# 8Bit-audio-7524-axelb-v2.net
KiCad netlist of a schematic drawn in EAGLE
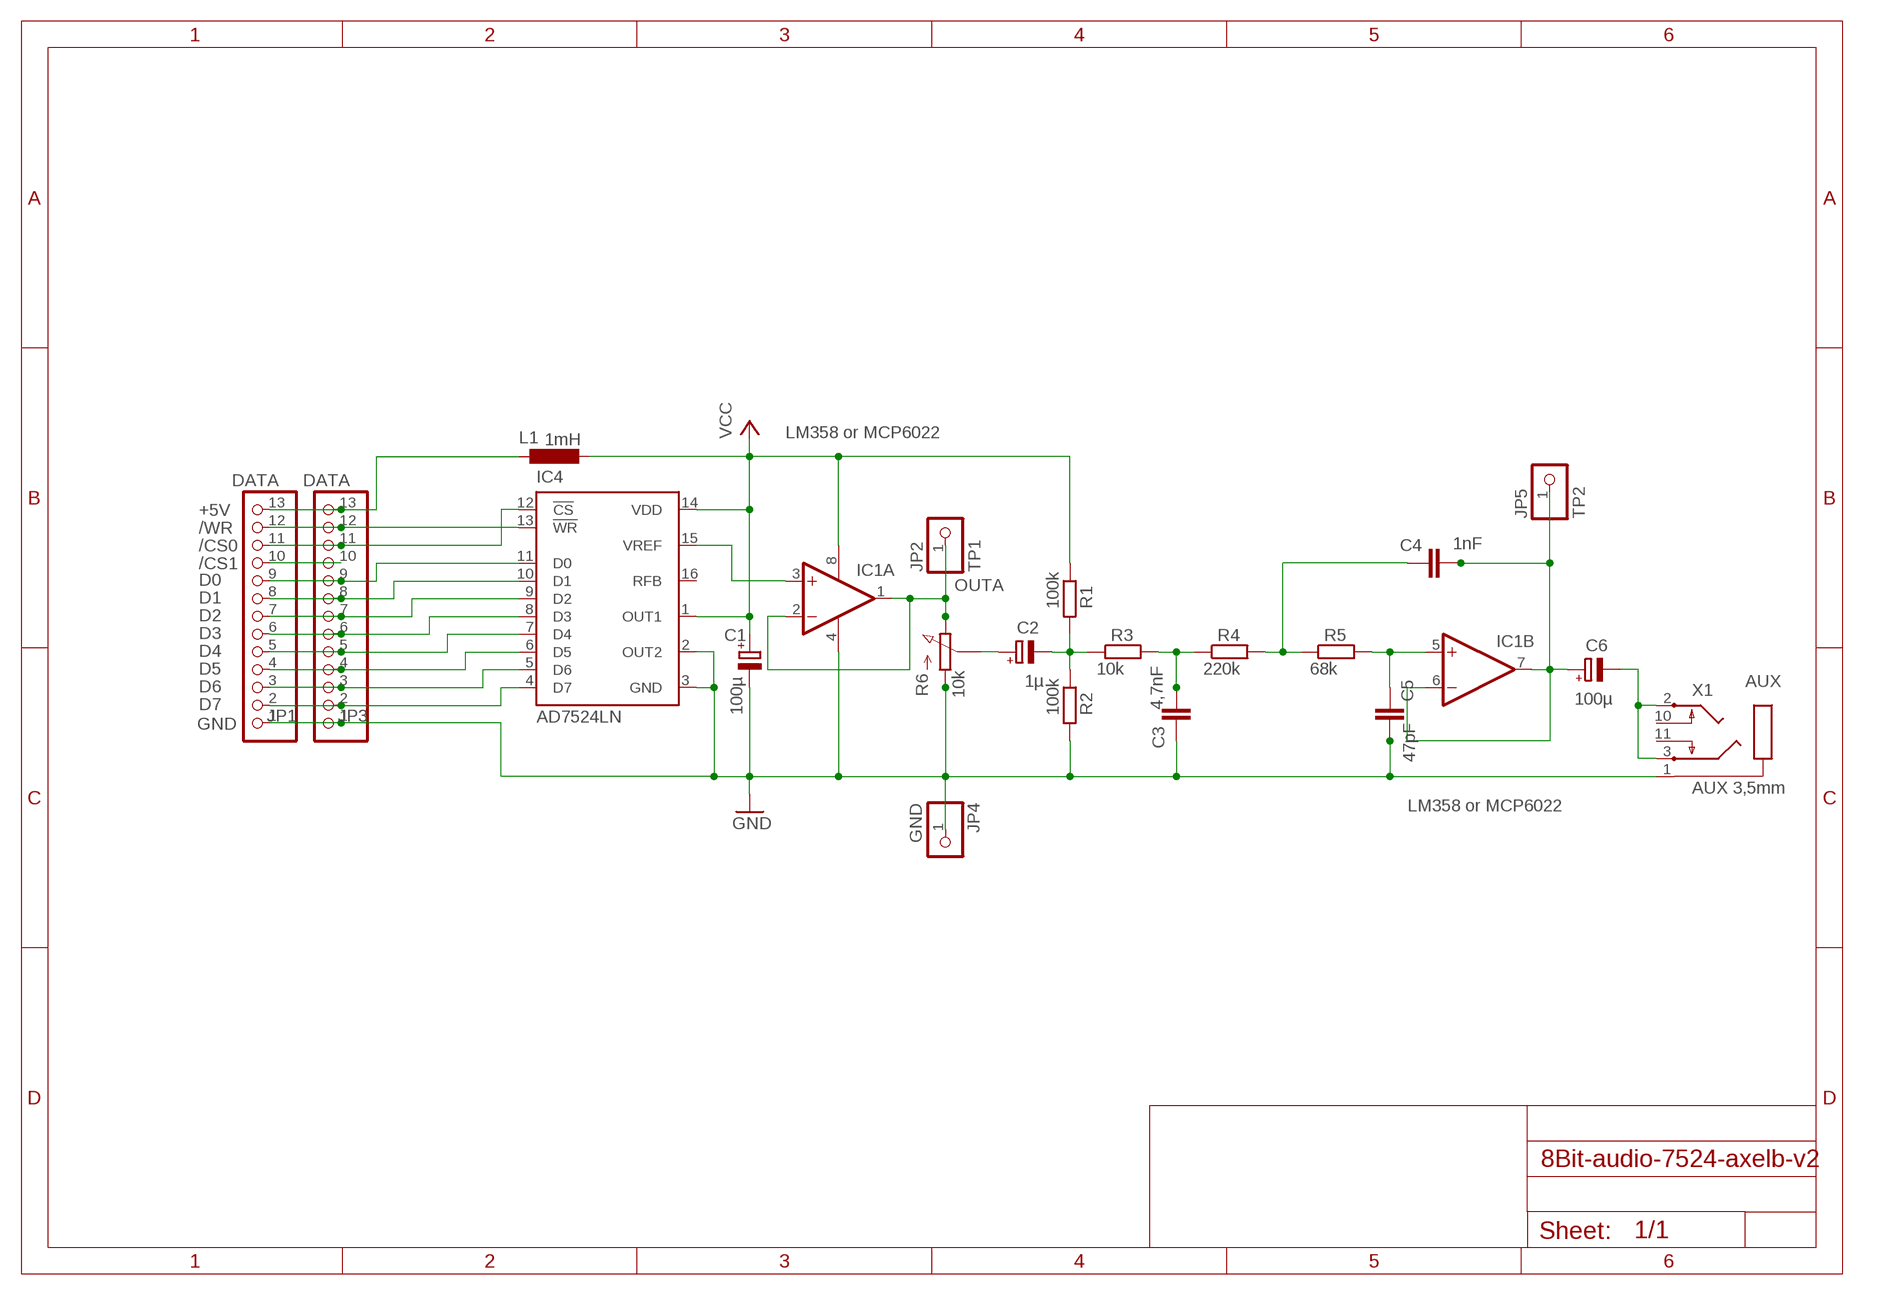
[diagram p0: schematic, sheet 1]

(export (version "E")
  (design (tool "Eeschema 10.0.6"))
  (components
    (comp (ref "C1")
      (value "100µ")
      (footprint "eagle-import:E5-5")
      (libsource (lib "eagle-import") (part "CPOL-EUE5-5"))
    )
    (comp (ref "C2")
      (value "1µ")
      (footprint "eagle-import:E5-5")
      (libsource (lib "eagle-import") (part "CPOL-EUE5-5"))
    )
    (comp (ref "C3")
      (value "4,7nF")
      (footprint "eagle-import:RCL_C025_050-055X075")
      (libsource (lib "eagle-import") (part "RCL_C-EU025_050-055X075"))
    )
    (comp (ref "C4")
      (value "1nF")
      (footprint "eagle-import:RCL_C025_050-055X075")
      (libsource (lib "eagle-import") (part "RCL_C-EU025_050-055X075"))
    )
    (comp (ref "C5")
      (value "47pF")
      (footprint "eagle-import:RCL_C025_050-055X075")
      (libsource (lib "eagle-import") (part "RCL_C-EU025_050-055X075"))
    )
    (comp (ref "C6")
      (value "100µ")
      (footprint "eagle-import:E5-5")
      (libsource (lib "eagle-import") (part "CPOL-EUE5-5"))
    )
    (comp (ref "IC1")
      (value "LM358 or MCP6022")
      (footprint "eagle-import:DIL08")
      (libsource (lib "eagle-import") (part "LM358N"))
    )
    (comp (ref "IC4")
      (value "AD7524LN")
      (footprint "eagle-import:DIL16")
      (fields (field (name "MF") "ALTERA CORPORATION") (field (name "MPN") "AD7524LNZ"))
      (libsource (lib "eagle-import") (part "AD7524NL"))
    )
    (comp (ref "JP1")
      (value "DATA")
      (footprint "eagle-import:1X13")
      (libsource (lib "eagle-import") (part "PINHD-1X13"))
    )
    (comp (ref "JP2")
      (value "TP1")
      (footprint "eagle-import:1X01")
      (libsource (lib "eagle-import") (part "PINHD-1X1"))
    )
    (comp (ref "JP3")
      (value "DATA")
      (footprint "eagle-import:1X13")
      (libsource (lib "eagle-import") (part "PINHD-1X13"))
    )
    (comp (ref "JP4")
      (value "GND")
      (footprint "eagle-import:1X01")
      (libsource (lib "eagle-import") (part "PINHD-1X1"))
    )
    (comp (ref "JP5")
      (value "TP2")
      (footprint "eagle-import:1X01")
      (libsource (lib "eagle-import") (part "PINHD-1X1"))
    )
    (comp (ref "L1")
      (value "1mH")
      (footprint "eagle-import:0207_10")
      (libsource (lib "eagle-import") (part "L-EU0207/10"))
    )
    (comp (ref "R1")
      (value "100k")
      (footprint "eagle-import:0207_10")
      (libsource (lib "eagle-import") (part "R-EU_0207/10"))
    )
    (comp (ref "R2")
      (value "100k")
      (footprint "eagle-import:0207_10")
      (libsource (lib "eagle-import") (part "R-EU_0207/10"))
    )
    (comp (ref "R3")
      (value "10k")
      (footprint "eagle-import:0207_10")
      (libsource (lib "eagle-import") (part "R-EU_0207/10"))
    )
    (comp (ref "R4")
      (value "220k")
      (footprint "eagle-import:0207_10")
      (libsource (lib "eagle-import") (part "R-EU_0207/10"))
    )
    (comp (ref "R5")
      (value "68k")
      (footprint "eagle-import:0207_10")
      (libsource (lib "eagle-import") (part "R-EU_0207/10"))
    )
    (comp (ref "R6")
      (value "10k")
      (footprint "eagle-import:POT_3RP_1610N")
      (libsource (lib "eagle-import") (part "POT_3RP/1610N"))
    )
    (comp (ref "X1")
      (value "AUX 3,5mm")
      (footprint "eagle-import:SJ1-352XN")
      (libsource (lib "eagle-import") (part "CON-SJ1-352XNSJ1-352XN"))
    )
  )
  (nets
    (net (code "1") (name "/+5V") (class "Default")
      (node (ref "JP1") (pin "13") (pinfunction "13_13") (pintype "passive"))
      (node (ref "JP3") (pin "13") (pinfunction "13_13") (pintype "passive"))
      (node (ref "L1") (pin "1") (pinfunction "1_1") (pintype "passive"))
    )
    (net (code "2") (name "/AUX") (class "Default")
      (node (ref "C6") (pin "-") (pinfunction "-_-") (pintype "passive"))
      (node (ref "X1") (pin "2") (pinfunction "2_2") (pintype "passive"))
      (node (ref "X1") (pin "3") (pinfunction "3_3") (pintype "passive"))
    )
    (net (code "3") (name "/D0") (class "Default")
      (node (ref "IC4") (pin "11") (pinfunction "D0_11") (pintype "input"))
      (node (ref "JP1") (pin "9") (pinfunction "9_9") (pintype "passive"))
      (node (ref "JP3") (pin "9") (pinfunction "9_9") (pintype "passive"))
    )
    (net (code "4") (name "/D1") (class "Default")
      (node (ref "IC4") (pin "10") (pinfunction "D1_10") (pintype "input"))
      (node (ref "JP1") (pin "8") (pinfunction "8_8") (pintype "passive"))
      (node (ref "JP3") (pin "8") (pinfunction "8_8") (pintype "passive"))
    )
    (net (code "5") (name "/D2") (class "Default")
      (node (ref "IC4") (pin "9") (pinfunction "D2_9") (pintype "input"))
      (node (ref "JP1") (pin "7") (pinfunction "7_7") (pintype "passive"))
      (node (ref "JP3") (pin "7") (pinfunction "7_7") (pintype "passive"))
    )
    (net (code "6") (name "/D3") (class "Default")
      (node (ref "IC4") (pin "8") (pinfunction "D3_8") (pintype "input"))
      (node (ref "JP1") (pin "6") (pinfunction "6_6") (pintype "passive"))
      (node (ref "JP3") (pin "6") (pinfunction "6_6") (pintype "passive"))
    )
    (net (code "7") (name "/D4") (class "Default")
      (node (ref "IC4") (pin "7") (pinfunction "D4_7") (pintype "input"))
      (node (ref "JP1") (pin "5") (pinfunction "5_5") (pintype "passive"))
      (node (ref "JP3") (pin "5") (pinfunction "5_5") (pintype "passive"))
    )
    (net (code "8") (name "/D5") (class "Default")
      (node (ref "IC4") (pin "6") (pinfunction "D5_6") (pintype "input"))
      (node (ref "JP1") (pin "4") (pinfunction "4_4") (pintype "passive"))
      (node (ref "JP3") (pin "4") (pinfunction "4_4") (pintype "passive"))
    )
    (net (code "9") (name "/D6") (class "Default")
      (node (ref "IC4") (pin "5") (pinfunction "D6_5") (pintype "input"))
      (node (ref "JP1") (pin "3") (pinfunction "3_3") (pintype "passive"))
      (node (ref "JP3") (pin "3") (pinfunction "3_3") (pintype "passive"))
    )
    (net (code "10") (name "/D7") (class "Default")
      (node (ref "IC4") (pin "4") (pinfunction "D7_4") (pintype "input"))
      (node (ref "JP1") (pin "2") (pinfunction "2_2") (pintype "passive"))
      (node (ref "JP3") (pin "2") (pinfunction "2_2") (pintype "passive"))
    )
    (net (code "11") (name "/OUTA") (class "Default")
      (node (ref "IC1") (pin "1") (pinfunction "OUT_1") (pintype "output"))
      (node (ref "IC1") (pin "2") (pinfunction "-IN_2") (pintype "input"))
      (node (ref "JP2") (pin "1") (pinfunction "1_1") (pintype "passive"))
      (node (ref "R6") (pin "E1") (pinfunction "E1_E1") (pintype "passive"))
      (node (ref "R6") (pin "E2") (pinfunction "E2_E2") (pintype "passive"))
    )
    (net (code "12") (name "/{slash}CS0") (class "Default")
      (node (ref "IC4") (pin "12") (pinfunction "~{CS}_12") (pintype "input"))
      (node (ref "JP1") (pin "11") (pinfunction "11_11") (pintype "passive"))
      (node (ref "JP3") (pin "11") (pinfunction "11_11") (pintype "passive"))
    )
    (net (code "13") (name "/{slash}CS1") (class "Default")
      (node (ref "JP1") (pin "10") (pinfunction "10_10") (pintype "passive"))
      (node (ref "JP3") (pin "10") (pinfunction "10_10") (pintype "passive"))
    )
    (net (code "14") (name "/{slash}WR") (class "Default")
      (node (ref "IC4") (pin "13") (pinfunction "~{WR}_13") (pintype "input"))
      (node (ref "JP1") (pin "12") (pinfunction "12_12") (pintype "passive"))
      (node (ref "JP3") (pin "12") (pinfunction "12_12") (pintype "passive"))
    )
    (net (code "15") (name "GND") (class "Default")
      (node (ref "C1") (pin "-") (pinfunction "-_-") (pintype "passive"))
      (node (ref "C3") (pin "1") (pinfunction "A1_1") (pintype "passive"))
      (node (ref "C5") (pin "2") (pinfunction "B1_2") (pintype "passive"))
      (node (ref "C5") (pin "3") (pinfunction "B2_3") (pintype "passive"))
      (node (ref "IC1") (pin "4") (pinfunction "V-_4") (pintype "power_in"))
      (node (ref "IC4") (pin "2") (pinfunction "OUT2_2") (pintype "passive"))
      (node (ref "IC4") (pin "3") (pinfunction "GND_3") (pintype "power_in"))
      (node (ref "JP1") (pin "1") (pinfunction "1_1") (pintype "passive"))
      (node (ref "JP3") (pin "1") (pinfunction "1_1") (pintype "passive"))
      (node (ref "JP4") (pin "1") (pinfunction "1_1") (pintype "passive"))
      (node (ref "R2") (pin "2") (pinfunction "2_2") (pintype "passive"))
      (node (ref "R6") (pin "A1") (pinfunction "A1_A1") (pintype "passive"))
      (node (ref "R6") (pin "A2") (pinfunction "A2_A2") (pintype "passive"))
      (node (ref "X1") (pin "1") (pinfunction "1_1") (pintype "passive"))
    )
    (net (code "16") (name "Net-(C2-Pad-)") (class "Default")
      (node (ref "C2") (pin "-") (pinfunction "-_-") (pintype "passive"))
      (node (ref "R1") (pin "2") (pinfunction "2_2") (pintype "passive"))
      (node (ref "R2") (pin "1") (pinfunction "1_1") (pintype "passive"))
      (node (ref "R3") (pin "1") (pinfunction "1_1") (pintype "passive"))
    )
    (net (code "17") (name "Net-(C3-B1)") (class "Default")
      (node (ref "C3") (pin "2") (pinfunction "B1_2") (pintype "passive"))
      (node (ref "C3") (pin "3") (pinfunction "B2_3") (pintype "passive"))
      (node (ref "R3") (pin "2") (pinfunction "2_2") (pintype "passive"))
      (node (ref "R4") (pin "1") (pinfunction "1_1") (pintype "passive"))
    )
    (net (code "18") (name "Net-(C4-A1)") (class "Default")
      (node (ref "C4") (pin "1") (pinfunction "A1_1") (pintype "passive"))
      (node (ref "R4") (pin "2") (pinfunction "2_2") (pintype "passive"))
      (node (ref "R5") (pin "1") (pinfunction "1_1") (pintype "passive"))
    )
    (net (code "19") (name "Net-(C4-B1)") (class "Default")
      (node (ref "C4") (pin "2") (pinfunction "B1_2") (pintype "passive"))
      (node (ref "C4") (pin "3") (pinfunction "B2_3") (pintype "passive"))
      (node (ref "C6") (pin "+") (pinfunction "+_+") (pintype "passive"))
      (node (ref "IC1") (pin "6") (pinfunction "-IN_6") (pintype "input"))
      (node (ref "IC1") (pin "7") (pinfunction "OUT_7") (pintype "output"))
      (node (ref "JP5") (pin "1") (pinfunction "1_1") (pintype "passive"))
    )
    (net (code "20") (name "Net-(C5-A1)") (class "Default")
      (node (ref "C5") (pin "1") (pinfunction "A1_1") (pintype "passive"))
      (node (ref "IC1") (pin "5") (pinfunction "+IN_5") (pintype "input"))
      (node (ref "R5") (pin "2") (pinfunction "2_2") (pintype "passive"))
    )
    (net (code "21") (name "Net-(IC1A-+IN)") (class "Default")
      (node (ref "IC1") (pin "3") (pinfunction "+IN_3") (pintype "input"))
      (node (ref "IC4") (pin "15") (pinfunction "VREF_15") (pintype "input"))
    )
    (net (code "22") (name "Net-(R6-S)") (class "Default")
      (node (ref "C2") (pin "+") (pinfunction "+_+") (pintype "passive"))
      (node (ref "R6") (pin "M") (pinfunction "S_M") (pintype "passive"))
    )
    (net (code "23") (name "VCC") (class "Default")
      (node (ref "C1") (pin "+") (pinfunction "+_+") (pintype "passive"))
      (node (ref "IC1") (pin "8") (pinfunction "V+_8") (pintype "power_in"))
      (node (ref "IC4") (pin "1") (pinfunction "OUT1_1") (pintype "passive"))
      (node (ref "IC4") (pin "14") (pinfunction "VDD_14") (pintype "power_in"))
      (node (ref "L1") (pin "2") (pinfunction "2_2") (pintype "passive"))
      (node (ref "R1") (pin "1") (pinfunction "1_1") (pintype "passive"))
    )
    (net (code "24") (name "unconnected-(IC4-RFB-Pad16)") (class "Default")
      (node (ref "IC4") (pin "16") (pinfunction "RFB_16") (pintype "passive"))
    )
    (net (code "25") (name "unconnected-(X1-Pad10)") (class "Default")
      (node (ref "X1") (pin "10") (pinfunction "10_10") (pintype "passive"))
    )
    (net (code "26") (name "unconnected-(X1-Pad11)") (class "Default")
      (node (ref "X1") (pin "11") (pinfunction "11_11") (pintype "passive"))
    )
  )
)
